# rapidshark-half-assed-half-h-bridge-mk-1.net
KiCad netlist of a schematic drawn in EAGLE
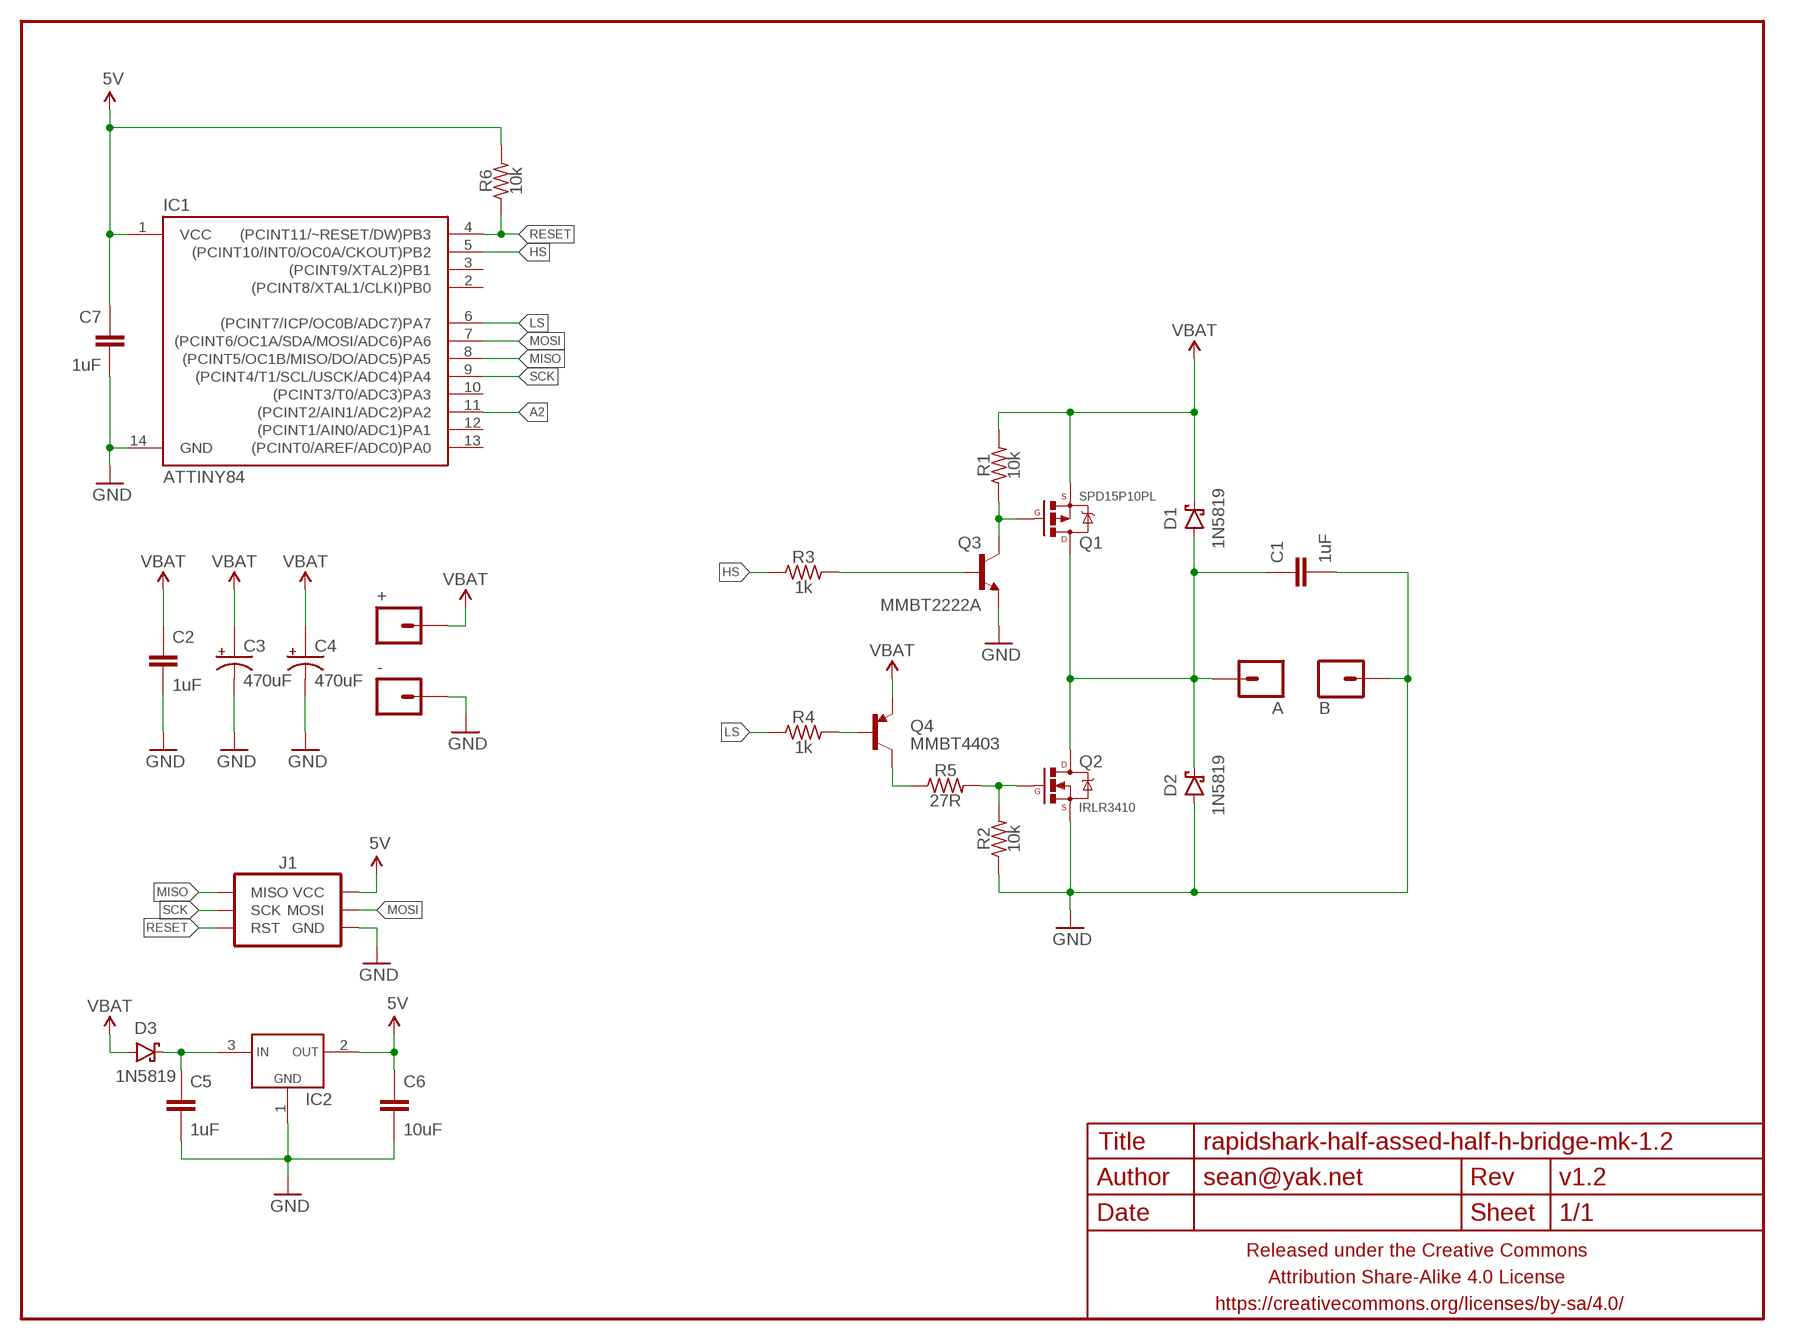
[diagram p0: schematic, sheet 1]

(export (version "E")
  (design (tool "Eeschema 10.0.6"))
  (components
    (comp (ref "+")
      (value "M01PTH-1.4MM")
      (footprint "eagle-import:1X01-1.4MM-CIR")
      (libsource (lib "eagle-import") (part "M01PTH-1.4MM"))
    )
    (comp (ref "-")
      (value "M01PTH-1.4MM")
      (footprint "eagle-import:1X01-1.4MM-CIR")
      (libsource (lib "eagle-import") (part "M01PTH-1.4MM"))
    )
    (comp (ref "A")
      (value "M01PTH-1.4MM")
      (footprint "eagle-import:1X01-1.4MM-CIR")
      (libsource (lib "eagle-import") (part "M01PTH-1.4MM"))
    )
    (comp (ref "B")
      (value "M01PTH-1.4MM")
      (footprint "eagle-import:1X01-1.4MM-CIR")
      (libsource (lib "eagle-import") (part "M01PTH-1.4MM"))
    )
    (comp (ref "C1")
      (value "1uF")
      (footprint "eagle-import:C0603-TIGHTER")
      (libsource (lib "eagle-import") (part "CAPACITOR-CERAMICC0603-TIGHTER"))
    )
    (comp (ref "C2")
      (value "1uF")
      (footprint "eagle-import:C0603-TIGHTER")
      (libsource (lib "eagle-import") (part "CAPACITOR-CERAMICC0603-TIGHTER"))
    )
    (comp (ref "C3")
      (value "470uF")
      (footprint "eagle-import:E5-10,5")
      (libsource (lib "eagle-import") (part "CAPACITOR-POLARIZEDE5-10.5"))
    )
    (comp (ref "C4")
      (value "470uF")
      (footprint "eagle-import:E5-10,5")
      (libsource (lib "eagle-import") (part "CAPACITOR-POLARIZEDE5-10.5"))
    )
    (comp (ref "C5")
      (value "1uF")
      (footprint "eagle-import:C0805-TIGHTER")
      (libsource (lib "eagle-import") (part "CAPACITOR-CERAMICC0805-TIGHTER"))
    )
    (comp (ref "C6")
      (value "10uF")
      (footprint "eagle-import:C0805-TIGHTER")
      (libsource (lib "eagle-import") (part "CAPACITOR-CERAMICC0805-TIGHTER"))
    )
    (comp (ref "C7")
      (value "1uF")
      (footprint "eagle-import:C0603-TIGHTER")
      (libsource (lib "eagle-import") (part "CAPACITOR-CERAMICC0603-TIGHTER"))
    )
    (comp (ref "D1")
      (value "1N5819")
      (footprint "eagle-import:SMA-DIODE-SCHOTTKY")
      (libsource (lib "eagle-import") (part "DIODE-SCHOTTKYSMA"))
    )
    (comp (ref "D2")
      (value "1N5819")
      (footprint "eagle-import:SMA-DIODE-SCHOTTKY")
      (libsource (lib "eagle-import") (part "DIODE-SCHOTTKYSMA"))
    )
    (comp (ref "D3")
      (value "1N5819")
      (footprint "eagle-import:SOD323-SCHOTTKY")
      (libsource (lib "eagle-import") (part "DIODE-SCHOTTKYSOD323"))
    )
    (comp (ref "FRAME1")
      (value "FRAME-LETTERNO_PACKAGE")
      (footprint "eagle-import:DUMMY")
      (fields (field (name "DESIGNER") "sean@yak.net") (field (name "VERSION") "v1.2"))
      (libsource (lib "eagle-import") (part "FRAME-LETTERNO_PACKAGE"))
    )
    (comp (ref "IC1")
      (value "ATTINY84")
      (footprint "eagle-import:SO14")
      (libsource (lib "eagle-import") (part "ATTINY84"))
    )
    (comp (ref "IC2")
      (value "VREG_1117SOT-23")
      (footprint "eagle-import:SOT23")
      (libsource (lib "eagle-import") (part "VREG_1117SOT-23"))
    )
    (comp (ref "J1")
      (value "AVR_SPI_PRG_6INLINE")
      (footprint "eagle-import:AVR_MINI_PROG")
      (libsource (lib "eagle-import") (part "AVR_SPI_PRG_6INLINE"))
    )
    (comp (ref "Q1")
      (value "SPD15P10PL")
      (footprint "eagle-import:DPAK")
      (libsource (lib "eagle-import") (part "MOSFET-PCHANNELDPAK"))
    )
    (comp (ref "Q2")
      (value "IRLR3410")
      (footprint "eagle-import:DPAK")
      (libsource (lib "eagle-import") (part "MOSFET-NCHANNELFDD8780"))
    )
    (comp (ref "Q3")
      (value "MMBT2222A")
      (footprint "eagle-import:SOT23")
      (libsource (lib "eagle-import") (part "TRANSISTOR_NPNMMBT2222A"))
    )
    (comp (ref "Q4")
      (value "MMBT4403")
      (footprint "eagle-import:SOT23")
      (libsource (lib "eagle-import") (part "TRANSISTOR_PNPMMBT4403"))
    )
    (comp (ref "R1")
      (value "10k")
      (footprint "eagle-import:R0603-TIGHTER")
      (libsource (lib "eagle-import") (part "RESISTORR0603-TIGHTER"))
    )
    (comp (ref "R2")
      (value "10k")
      (footprint "eagle-import:R0603-TIGHTER")
      (libsource (lib "eagle-import") (part "RESISTORR0603-TIGHTER"))
    )
    (comp (ref "R3")
      (value "1k")
      (footprint "eagle-import:R0603-TIGHTER")
      (libsource (lib "eagle-import") (part "RESISTORR0603-TIGHTER"))
    )
    (comp (ref "R4")
      (value "1k")
      (footprint "eagle-import:R0603-TIGHTER")
      (libsource (lib "eagle-import") (part "RESISTORR0603-TIGHTER"))
    )
    (comp (ref "R5")
      (value "27R")
      (footprint "eagle-import:R0603-TIGHTER")
      (libsource (lib "eagle-import") (part "RESISTORR0603-TIGHTER"))
    )
    (comp (ref "R6")
      (value "10k")
      (footprint "eagle-import:R0603-TIGHTER")
      (libsource (lib "eagle-import") (part "RESISTORR0603-TIGHTER"))
    )
  )
  (nets
    (net (code "1") (name "5V") (class "Default")
      (node (ref "C6") (pin "1") (pinfunction "1_1") (pintype "passive"))
      (node (ref "C7") (pin "1") (pinfunction "1_1") (pintype "passive"))
      (node (ref "IC1") (pin "1") (pinfunction "VCC_1") (pintype "bidirectional"))
      (node (ref "IC2") (pin "2") (pinfunction "VOUT_2") (pintype "bidirectional"))
      (node (ref "J1") (pin "2") (pinfunction "VCC_2") (pintype "passive"))
      (node (ref "R6") (pin "2") (pinfunction "2_2") (pintype "passive"))
    )
    (net (code "2") (name "A2") (class "Default")
      (node (ref "IC1") (pin "11") (pinfunction "(PCINT2/AIN1/ADC2)PA2_11") (pintype "bidirectional"))
    )
    (net (code "3") (name "GND") (class "Default")
      (node (ref "-") (pin "P$1") (pinfunction "1_P$1") (pintype "passive"))
      (node (ref "B") (pin "P$1") (pinfunction "1_P$1") (pintype "passive"))
      (node (ref "C1") (pin "2") (pinfunction "2_2") (pintype "passive"))
      (node (ref "C2") (pin "2") (pinfunction "2_2") (pintype "passive"))
      (node (ref "C3") (pin "-") (pinfunction "-_-") (pintype "passive"))
      (node (ref "C4") (pin "-") (pinfunction "-_-") (pintype "passive"))
      (node (ref "C5") (pin "2") (pinfunction "2_2") (pintype "passive"))
      (node (ref "C6") (pin "2") (pinfunction "2_2") (pintype "passive"))
      (node (ref "C7") (pin "2") (pinfunction "2_2") (pintype "passive"))
      (node (ref "D2") (pin "A") (pinfunction "A_A") (pintype "passive"))
      (node (ref "IC1") (pin "14") (pinfunction "GND_14") (pintype "bidirectional"))
      (node (ref "IC2") (pin "1") (pinfunction "GND_1") (pintype "bidirectional"))
      (node (ref "J1") (pin "6") (pinfunction "GND_6") (pintype "passive"))
      (node (ref "Q2") (pin "3") (pinfunction "S_3") (pintype "passive"))
      (node (ref "Q3") (pin "2") (pinfunction "E_2") (pintype "passive"))
      (node (ref "R2") (pin "1") (pinfunction "1_1") (pintype "passive"))
    )
    (net (code "4") (name "HS") (class "Default")
      (node (ref "IC1") (pin "5") (pinfunction "(PCINT10/INT0/OC0A/CKOUT)PB2_5") (pintype "bidirectional"))
      (node (ref "R3") (pin "1") (pinfunction "1_1") (pintype "passive"))
    )
    (net (code "5") (name "LS") (class "Default")
      (node (ref "IC1") (pin "6") (pinfunction "(PCINT7/ICP/OC0B/ADC7)PA7_6") (pintype "bidirectional"))
      (node (ref "R4") (pin "1") (pinfunction "1_1") (pintype "passive"))
    )
    (net (code "6") (name "MISO") (class "Default")
      (node (ref "IC1") (pin "8") (pinfunction "(PCINT5/OC1B/MISO/DO/ADC5)PA5_8") (pintype "bidirectional"))
      (node (ref "J1") (pin "1") (pinfunction "MISO_1") (pintype "passive"))
    )
    (net (code "7") (name "MOSI") (class "Default")
      (node (ref "IC1") (pin "7") (pinfunction "(PCINT6/OC1A/SDA/MOSI/ADC6)PA6_7") (pintype "bidirectional"))
      (node (ref "J1") (pin "4") (pinfunction "MOSI_4") (pintype "passive"))
    )
    (net (code "8") (name "Net-(A-1)") (class "Default")
      (node (ref "A") (pin "P$1") (pinfunction "1_P$1") (pintype "passive"))
      (node (ref "C1") (pin "1") (pinfunction "1_1") (pintype "passive"))
      (node (ref "D1") (pin "A") (pinfunction "A_A") (pintype "passive"))
      (node (ref "D2") (pin "C") (pinfunction "C_C") (pintype "passive"))
      (node (ref "Q1") (pin "4") (pinfunction "D_4") (pintype "passive"))
      (node (ref "Q2") (pin "4") (pinfunction "D_4") (pintype "passive"))
    )
    (net (code "9") (name "Net-(IC2-VIN)") (class "Default")
      (node (ref "C5") (pin "1") (pinfunction "1_1") (pintype "passive"))
      (node (ref "D3") (pin "C") (pinfunction "C_C") (pintype "passive"))
      (node (ref "IC2") (pin "3") (pinfunction "VIN_3") (pintype "bidirectional"))
    )
    (net (code "10") (name "Net-(Q1-G)") (class "Default")
      (node (ref "Q1") (pin "1") (pinfunction "G_1") (pintype "passive"))
      (node (ref "Q3") (pin "3") (pinfunction "C_3") (pintype "passive"))
      (node (ref "R1") (pin "1") (pinfunction "1_1") (pintype "passive"))
    )
    (net (code "11") (name "Net-(Q2-G)") (class "Default")
      (node (ref "Q2") (pin "1") (pinfunction "G_1") (pintype "passive"))
      (node (ref "R2") (pin "2") (pinfunction "2_2") (pintype "passive"))
      (node (ref "R5") (pin "2") (pinfunction "2_2") (pintype "passive"))
    )
    (net (code "12") (name "Net-(Q3-B)") (class "Default")
      (node (ref "Q3") (pin "1") (pinfunction "B_1") (pintype "passive"))
      (node (ref "R3") (pin "2") (pinfunction "2_2") (pintype "passive"))
    )
    (net (code "13") (name "Net-(Q4-B)") (class "Default")
      (node (ref "Q4") (pin "1") (pinfunction "B_1") (pintype "passive"))
      (node (ref "R4") (pin "2") (pinfunction "2_2") (pintype "passive"))
    )
    (net (code "14") (name "Net-(Q4-C)") (class "Default")
      (node (ref "Q4") (pin "3") (pinfunction "C_3") (pintype "passive"))
      (node (ref "R5") (pin "1") (pinfunction "1_1") (pintype "passive"))
    )
    (net (code "15") (name "RESET") (class "Default")
      (node (ref "IC1") (pin "4") (pinfunction "(PCINT11/~{RESET/DW})PB3_4") (pintype "bidirectional"))
      (node (ref "J1") (pin "5") (pinfunction "RST_5") (pintype "passive"))
      (node (ref "R6") (pin "1") (pinfunction "1_1") (pintype "passive"))
    )
    (net (code "16") (name "SCK") (class "Default")
      (node (ref "IC1") (pin "9") (pinfunction "(PCINT4/T1/SCL/USCK/ADC4)PA4_9") (pintype "bidirectional"))
      (node (ref "J1") (pin "3") (pinfunction "SCK_3") (pintype "passive"))
    )
    (net (code "17") (name "VBAT") (class "Default")
      (node (ref "+") (pin "P$1") (pinfunction "1_P$1") (pintype "passive"))
      (node (ref "C2") (pin "1") (pinfunction "1_1") (pintype "passive"))
      (node (ref "C3") (pin "+") (pinfunction "+_+") (pintype "passive"))
      (node (ref "C4") (pin "+") (pinfunction "+_+") (pintype "passive"))
      (node (ref "D1") (pin "C") (pinfunction "C_C") (pintype "passive"))
      (node (ref "D3") (pin "A") (pinfunction "A_A") (pintype "passive"))
      (node (ref "Q1") (pin "3") (pinfunction "S_3") (pintype "passive"))
      (node (ref "Q4") (pin "2") (pinfunction "E_2") (pintype "passive"))
      (node (ref "R1") (pin "2") (pinfunction "2_2") (pintype "passive"))
    )
    (net (code "18") (name "unconnected-(IC1-(PCINT0{slash}AREF{slash}ADC0)PA0-Pad13)") (class "Default")
      (node (ref "IC1") (pin "13") (pinfunction "(PCINT0/AREF/ADC0)PA0_13") (pintype "bidirectional"))
    )
    (net (code "19") (name "unconnected-(IC1-(PCINT1{slash}AIN0{slash}ADC1)PA1-Pad12)") (class "Default")
      (node (ref "IC1") (pin "12") (pinfunction "(PCINT1/AIN0/ADC1)PA1_12") (pintype "bidirectional"))
    )
    (net (code "20") (name "unconnected-(IC1-(PCINT3{slash}T0{slash}ADC3)PA3-Pad10)") (class "Default")
      (node (ref "IC1") (pin "10") (pinfunction "(PCINT3/T0/ADC3)PA3_10") (pintype "bidirectional"))
    )
    (net (code "21") (name "unconnected-(IC1-(PCINT8{slash}XTAL1{slash}CLKI)PB0-Pad2)") (class "Default")
      (node (ref "IC1") (pin "2") (pinfunction "(PCINT8/XTAL1/CLKI)PB0_2") (pintype "bidirectional"))
    )
    (net (code "22") (name "unconnected-(IC1-(PCINT9{slash}XTAL2)PB1-Pad3)") (class "Default")
      (node (ref "IC1") (pin "3") (pinfunction "(PCINT9/XTAL2)PB1_3") (pintype "bidirectional"))
    )
  )
)
